# ESP32.net
KiCad netlist of a schematic drawn in Altium Designer
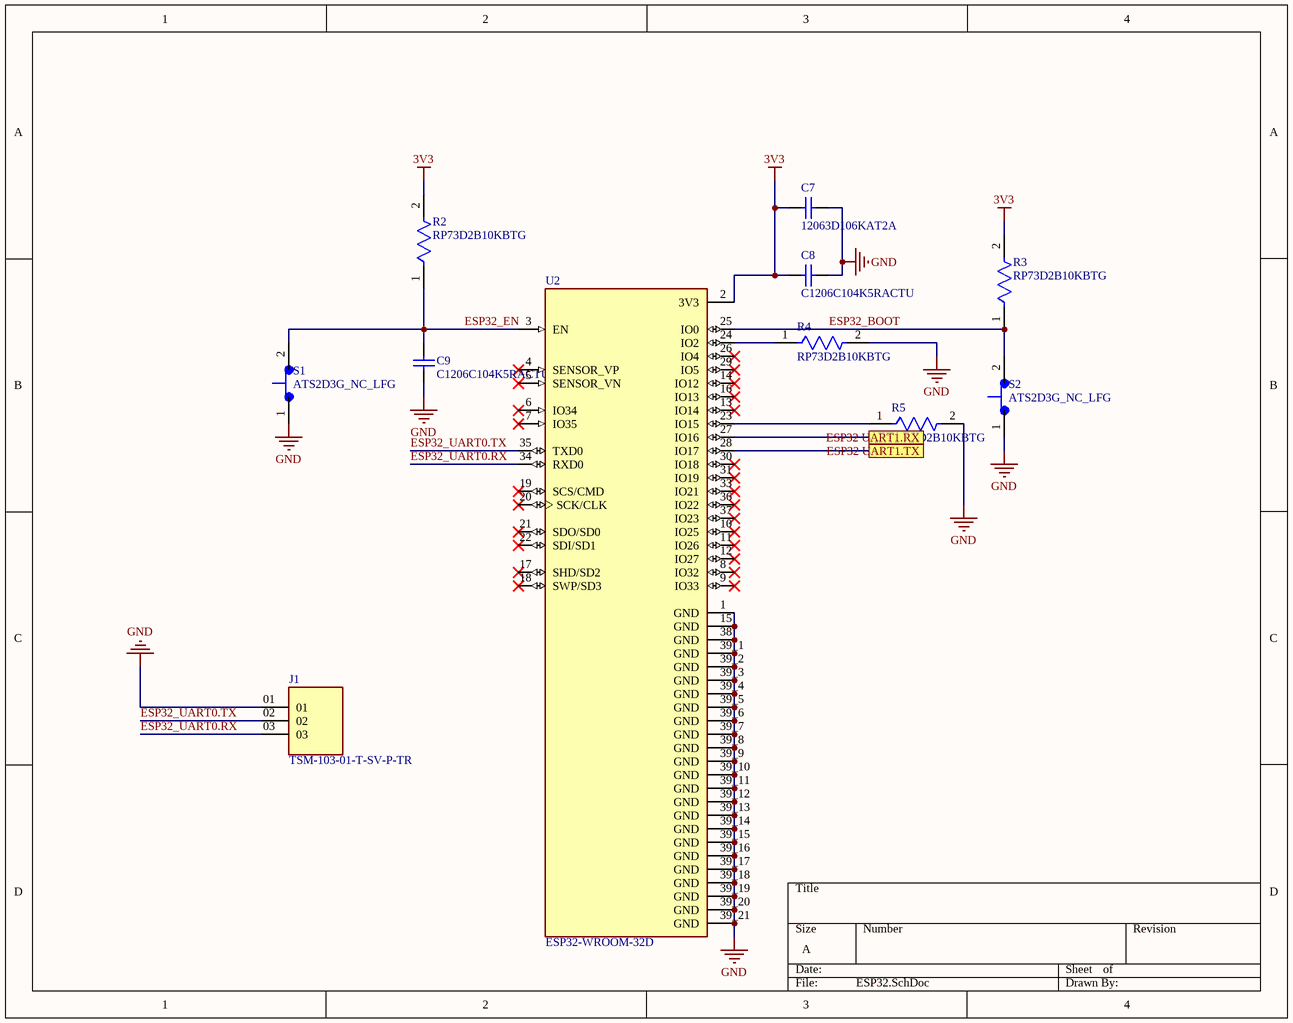
[diagram p0: ESP32.SchDoc]

(export (version "E")
  (design (tool "Eeschema 10.0.6"))
  (components
    (comp (ref "C7")
      (value "12063D106KAT2A")
      (footprint "CAPC3216X229X50LL20T25")
      (description "Chip Capacitor, 10 uF, +/- 10%, 25 V, -55 to 85 degC, 1206 (3216 Metric), RoHS, Tape and Reel")
      (fields (field (name "MANUFACTURER") "AVX"))
      (libsource (lib "Altium Content Vault") (part "CAP-NP-2"))
    )
    (comp (ref "C8")
      (value "C1206C104K5RACTU")
      (footprint "KEMT-1206-2_M")
      (description "CAP, Ceramic, 0.1 uF, +/- 10%, 50 V, -55 to 125 degC, 1206 (3216 Metric), RoHS, Tape and Reel")
      (fields (field (name "MANUFACTURER") "Kemet"))
      (libsource (lib "Altium Content Vault") (part "CAP-NP-2"))
    )
    (comp (ref "C9")
      (value "C1206C104K5RACTU")
      (footprint "KEMT-1206-2_M")
      (description "CAP, Ceramic, 0.1 uF, +/- 10%, 50 V, -55 to 125 degC, 1206 (3216 Metric), RoHS, Tape and Reel")
      (fields (field (name "MANUFACTURER") "Kemet"))
      (libsource (lib "Altium Content Vault") (part "CAP-NP-2"))
    )
    (comp (ref "J1")
      (value "TSM-103-01-T-SV-P-TR")
      (footprint "SAMTEC_TSM-103-01-T-SV-P-TR")
      (fields (field (name "MF") "Samtec"))
      (libsource (lib "TSM-103-01-T-SV-P-TR") (part "TSM-103-01-T-SV-P-TR"))
    )
    (comp (ref "R2")
      (value "RP73D2B10KBTG")
      (footprint "FP-RP732B-MFG")
      (description "Res Thin Film 1206 10KΩ 0.1% 0.25W 15ppm/°C Molded SMD")
      (fields
        (field (name "MANUFACTURER") "TE Connectivity")
        (field (name "OCTOPART") "https://octopart.com/rp73d2b10kbtg-te+connectivity-42012630")
      )
      (libsource (lib "Altium Content Vault") (part "1029c3af85768c4190bb7ad29bc67b5"))
    )
    (comp (ref "R3")
      (value "RP73D2B10KBTG")
      (footprint "FP-RP732B-MFG")
      (description "Res Thin Film 1206 10KΩ 0.1% 0.25W 15ppm/°C Molded SMD")
      (fields
        (field (name "MANUFACTURER") "TE Connectivity")
        (field (name "OCTOPART") "https://octopart.com/rp73d2b10kbtg-te+connectivity-42012630")
      )
      (libsource (lib "Altium Content Vault") (part "1029c3af85768c4190bb7ad29bc67b5"))
    )
    (comp (ref "R4")
      (value "RP73D2B10KBTG")
      (footprint "FP-RP732B-MFG")
      (description "Res Thin Film 1206 10KΩ 0.1% 0.25W 15ppm/°C Molded SMD")
      (fields
        (field (name "MANUFACTURER") "TE Connectivity")
        (field (name "OCTOPART") "https://octopart.com/rp73d2b10kbtg-te+connectivity-42012630")
      )
      (libsource (lib "Altium Content Vault") (part "1029c3af85768c4190bb7ad29bc67b5"))
    )
    (comp (ref "R5")
      (value "RP73D2B10KBTG")
      (footprint "FP-RP732B-MFG")
      (description "Res Thin Film 1206 10KΩ 0.1% 0.25W 15ppm/°C Molded SMD")
      (fields
        (field (name "MANUFACTURER") "TE Connectivity")
        (field (name "OCTOPART") "https://octopart.com/rp73d2b10kbtg-te+connectivity-42012630")
      )
      (libsource (lib "Altium Content Vault") (part "1029c3af85768c4190bb7ad29bc67b5"))
    )
    (comp (ref "S1")
      (value "ATS2D3G_NC_LFG")
      (footprint "SW_ATS2D3G_NC_LFG")
      (description "Tactile Switch SPST-NC Top Actuated Surface Mount")
      (libsource (lib "ATS2D3G_NC_LFG") (part "ATS2D3G_NC_LFG"))
    )
    (comp (ref "S2")
      (value "ATS2D3G_NC_LFG")
      (footprint "SW_ATS2D3G_NC_LFG")
      (description "Tactile Switch SPST-NC Top Actuated Surface Mount")
      (libsource (lib "ATS2D3G_NC_LFG") (part "ATS2D3G_NC_LFG"))
    )
    (comp (ref "U2")
      (value "ESP32-WROOM-32D")
      (footprint "MODULE_ESP32-WROOM-32D")
      (fields (field (name "MF") "Espressif Systems"))
      (libsource (lib "ESP32-WROOM-32D") (part "ESP32-WROOM-32D"))
    )
  )
  (nets
    (net (code "1") (name "/ESP32 UART1.RX") (class "Default")
      (node (ref "U2") (pin "27") (pinfunction "IO16_27") (pintype "bidirectional"))
    )
    (net (code "2") (name "/ESP32 UART1.TX") (class "Default")
      (node (ref "U2") (pin "28") (pinfunction "IO17_28") (pintype "bidirectional"))
    )
    (net (code "3") (name "/ESP32_BOOT") (class "Default")
      (node (ref "R3") (pin "1") (pinfunction "1_1") (pintype "passive"))
      (node (ref "S2") (pin "2") (pinfunction "2_2") (pintype "passive"))
      (node (ref "U2") (pin "25") (pinfunction "IO0_25") (pintype "bidirectional"))
    )
    (net (code "4") (name "/ESP32_EN") (class "Default")
      (node (ref "C9") (pin "2") (pinfunction "2_2") (pintype "passive"))
      (node (ref "R2") (pin "1") (pinfunction "1_1") (pintype "passive"))
      (node (ref "S1") (pin "2") (pinfunction "2_2") (pintype "passive"))
      (node (ref "U2") (pin "3") (pinfunction "EN_3") (pintype "input"))
    )
    (net (code "5") (name "/ESP32_UART0.RX") (class "Default")
      (node (ref "J1") (pin "03") (pinfunction "03_03") (pintype "passive"))
      (node (ref "U2") (pin "34") (pinfunction "RXD0_34") (pintype "bidirectional"))
    )
    (net (code "6") (name "/ESP32_UART0.TX") (class "Default")
      (node (ref "J1") (pin "02") (pinfunction "02_02") (pintype "passive"))
      (node (ref "U2") (pin "35") (pinfunction "TXD0_35") (pintype "bidirectional"))
    )
    (net (code "7") (name "3V3") (class "Default")
      (node (ref "C7") (pin "1") (pinfunction "1_1") (pintype "passive"))
      (node (ref "C8") (pin "1") (pinfunction "1_1") (pintype "passive"))
      (node (ref "R2") (pin "2") (pinfunction "2_2") (pintype "passive"))
      (node (ref "R3") (pin "2") (pinfunction "2_2") (pintype "passive"))
      (node (ref "U2") (pin "2") (pinfunction "3V3_2") (pintype "power_in"))
    )
    (net (code "8") (name "GND") (class "Default")
      (node (ref "C7") (pin "2") (pinfunction "2_2") (pintype "passive"))
      (node (ref "C8") (pin "2") (pinfunction "2_2") (pintype "passive"))
      (node (ref "C9") (pin "1") (pinfunction "1_1") (pintype "passive"))
      (node (ref "J1") (pin "01") (pinfunction "01_01") (pintype "passive"))
      (node (ref "R4") (pin "2") (pinfunction "2_2") (pintype "passive"))
      (node (ref "R5") (pin "2") (pinfunction "2_2") (pintype "passive"))
      (node (ref "S1") (pin "1") (pinfunction "1_1") (pintype "passive"))
      (node (ref "S2") (pin "1") (pinfunction "1_1") (pintype "passive"))
      (node (ref "U2") (pin "1") (pinfunction "GND_1") (pintype "power_in"))
      (node (ref "U2") (pin "15") (pinfunction "GND_15") (pintype "power_in"))
      (node (ref "U2") (pin "38") (pinfunction "GND_38") (pintype "power_in"))
      (node (ref "U2") (pin "39_1") (pinfunction "GND_39_1") (pintype "power_in"))
      (node (ref "U2") (pin "39_10") (pinfunction "GND_39_10") (pintype "power_in"))
      (node (ref "U2") (pin "39_11") (pinfunction "GND_39_11") (pintype "power_in"))
      (node (ref "U2") (pin "39_12") (pinfunction "GND_39_12") (pintype "power_in"))
      (node (ref "U2") (pin "39_13") (pinfunction "GND_39_13") (pintype "power_in"))
      (node (ref "U2") (pin "39_14") (pinfunction "GND_39_14") (pintype "power_in"))
      (node (ref "U2") (pin "39_15") (pinfunction "GND_39_15") (pintype "power_in"))
      (node (ref "U2") (pin "39_16") (pinfunction "GND_39_16") (pintype "power_in"))
      (node (ref "U2") (pin "39_17") (pinfunction "GND_39_17") (pintype "power_in"))
      (node (ref "U2") (pin "39_18") (pinfunction "GND_39_18") (pintype "power_in"))
      (node (ref "U2") (pin "39_19") (pinfunction "GND_39_19") (pintype "power_in"))
      (node (ref "U2") (pin "39_2") (pinfunction "GND_39_2") (pintype "power_in"))
      (node (ref "U2") (pin "39_20") (pinfunction "GND_39_20") (pintype "power_in"))
      (node (ref "U2") (pin "39_21") (pinfunction "GND_39_21") (pintype "power_in"))
      (node (ref "U2") (pin "39_3") (pinfunction "GND_39_3") (pintype "power_in"))
      (node (ref "U2") (pin "39_4") (pinfunction "GND_39_4") (pintype "power_in"))
      (node (ref "U2") (pin "39_5") (pinfunction "GND_39_5") (pintype "power_in"))
      (node (ref "U2") (pin "39_6") (pinfunction "GND_39_6") (pintype "power_in"))
      (node (ref "U2") (pin "39_7") (pinfunction "GND_39_7") (pintype "power_in"))
      (node (ref "U2") (pin "39_8") (pinfunction "GND_39_8") (pintype "power_in"))
      (node (ref "U2") (pin "39_9") (pinfunction "GND_39_9") (pintype "power_in"))
    )
    (net (code "9") (name "Net-(U2-IO2)") (class "Default")
      (node (ref "R4") (pin "1") (pinfunction "1_1") (pintype "passive"))
      (node (ref "U2") (pin "24") (pinfunction "IO2_24") (pintype "bidirectional"))
    )
    (net (code "10") (name "Net-(U2-IO15)") (class "Default")
      (node (ref "R5") (pin "1") (pinfunction "1_1") (pintype "passive"))
      (node (ref "U2") (pin "23") (pinfunction "IO15_23") (pintype "bidirectional"))
    )
    (net (code "11") (name "unconnected-(U2-IO4-Pad26)") (class "Default")
      (node (ref "U2") (pin "26") (pinfunction "IO4_26") (pintype "bidirectional+no_connect"))
    )
    (net (code "12") (name "unconnected-(U2-IO5-Pad29)") (class "Default")
      (node (ref "U2") (pin "29") (pinfunction "IO5_29") (pintype "bidirectional+no_connect"))
    )
    (net (code "13") (name "unconnected-(U2-IO12-Pad14)") (class "Default")
      (node (ref "U2") (pin "14") (pinfunction "IO12_14") (pintype "bidirectional+no_connect"))
    )
    (net (code "14") (name "unconnected-(U2-IO13-Pad16)") (class "Default")
      (node (ref "U2") (pin "16") (pinfunction "IO13_16") (pintype "bidirectional+no_connect"))
    )
    (net (code "15") (name "unconnected-(U2-IO14-Pad13)") (class "Default")
      (node (ref "U2") (pin "13") (pinfunction "IO14_13") (pintype "bidirectional+no_connect"))
    )
    (net (code "16") (name "unconnected-(U2-IO18-Pad30)") (class "Default")
      (node (ref "U2") (pin "30") (pinfunction "IO18_30") (pintype "bidirectional+no_connect"))
    )
    (net (code "17") (name "unconnected-(U2-IO19-Pad31)") (class "Default")
      (node (ref "U2") (pin "31") (pinfunction "IO19_31") (pintype "bidirectional+no_connect"))
    )
    (net (code "18") (name "unconnected-(U2-IO21-Pad33)") (class "Default")
      (node (ref "U2") (pin "33") (pinfunction "IO21_33") (pintype "bidirectional+no_connect"))
    )
    (net (code "19") (name "unconnected-(U2-IO22-Pad36)") (class "Default")
      (node (ref "U2") (pin "36") (pinfunction "IO22_36") (pintype "bidirectional+no_connect"))
    )
    (net (code "20") (name "unconnected-(U2-IO23-Pad37)") (class "Default")
      (node (ref "U2") (pin "37") (pinfunction "IO23_37") (pintype "bidirectional+no_connect"))
    )
    (net (code "21") (name "unconnected-(U2-IO25-Pad10)") (class "Default")
      (node (ref "U2") (pin "10") (pinfunction "IO25_10") (pintype "bidirectional+no_connect"))
    )
    (net (code "22") (name "unconnected-(U2-IO26-Pad11)") (class "Default")
      (node (ref "U2") (pin "11") (pinfunction "IO26_11") (pintype "bidirectional+no_connect"))
    )
    (net (code "23") (name "unconnected-(U2-IO27-Pad12)") (class "Default")
      (node (ref "U2") (pin "12") (pinfunction "IO27_12") (pintype "bidirectional+no_connect"))
    )
    (net (code "24") (name "unconnected-(U2-IO32-Pad8)") (class "Default")
      (node (ref "U2") (pin "8") (pinfunction "IO32_8") (pintype "bidirectional+no_connect"))
    )
    (net (code "25") (name "unconnected-(U2-IO33-Pad9)") (class "Default")
      (node (ref "U2") (pin "9") (pinfunction "IO33_9") (pintype "bidirectional+no_connect"))
    )
    (net (code "26") (name "unconnected-(U2-IO34-Pad6)") (class "Default")
      (node (ref "U2") (pin "6") (pinfunction "IO34_6") (pintype "input+no_connect"))
    )
    (net (code "27") (name "unconnected-(U2-IO35-Pad7)") (class "Default")
      (node (ref "U2") (pin "7") (pinfunction "IO35_7") (pintype "input+no_connect"))
    )
    (net (code "28") (name "unconnected-(U2-SCK{slash}CLK-Pad20)") (class "Default")
      (node (ref "U2") (pin "20") (pinfunction "SCK/CLK_20") (pintype "bidirectional+no_connect"))
    )
    (net (code "29") (name "unconnected-(U2-SCS{slash}CMD-Pad19)") (class "Default")
      (node (ref "U2") (pin "19") (pinfunction "SCS/CMD_19") (pintype "bidirectional+no_connect"))
    )
    (net (code "30") (name "unconnected-(U2-SDI{slash}SD1-Pad22)") (class "Default")
      (node (ref "U2") (pin "22") (pinfunction "SDI/SD1_22") (pintype "bidirectional+no_connect"))
    )
    (net (code "31") (name "unconnected-(U2-SDO{slash}SD0-Pad21)") (class "Default")
      (node (ref "U2") (pin "21") (pinfunction "SDO/SD0_21") (pintype "bidirectional+no_connect"))
    )
    (net (code "32") (name "unconnected-(U2-SENSOR_VN-Pad5)") (class "Default")
      (node (ref "U2") (pin "5") (pinfunction "SENSOR_VN_5") (pintype "input+no_connect"))
    )
    (net (code "33") (name "unconnected-(U2-SENSOR_VP-Pad4)") (class "Default")
      (node (ref "U2") (pin "4") (pinfunction "SENSOR_VP_4") (pintype "input+no_connect"))
    )
    (net (code "34") (name "unconnected-(U2-SHD{slash}SD2-Pad17)") (class "Default")
      (node (ref "U2") (pin "17") (pinfunction "SHD/SD2_17") (pintype "bidirectional+no_connect"))
    )
    (net (code "35") (name "unconnected-(U2-SWP{slash}SD3-Pad18)") (class "Default")
      (node (ref "U2") (pin "18") (pinfunction "SWP/SD3_18") (pintype "bidirectional+no_connect"))
    )
  )
)
